# radfet_supply.net
KiCad netlist of a schematic drawn in Altium Designer
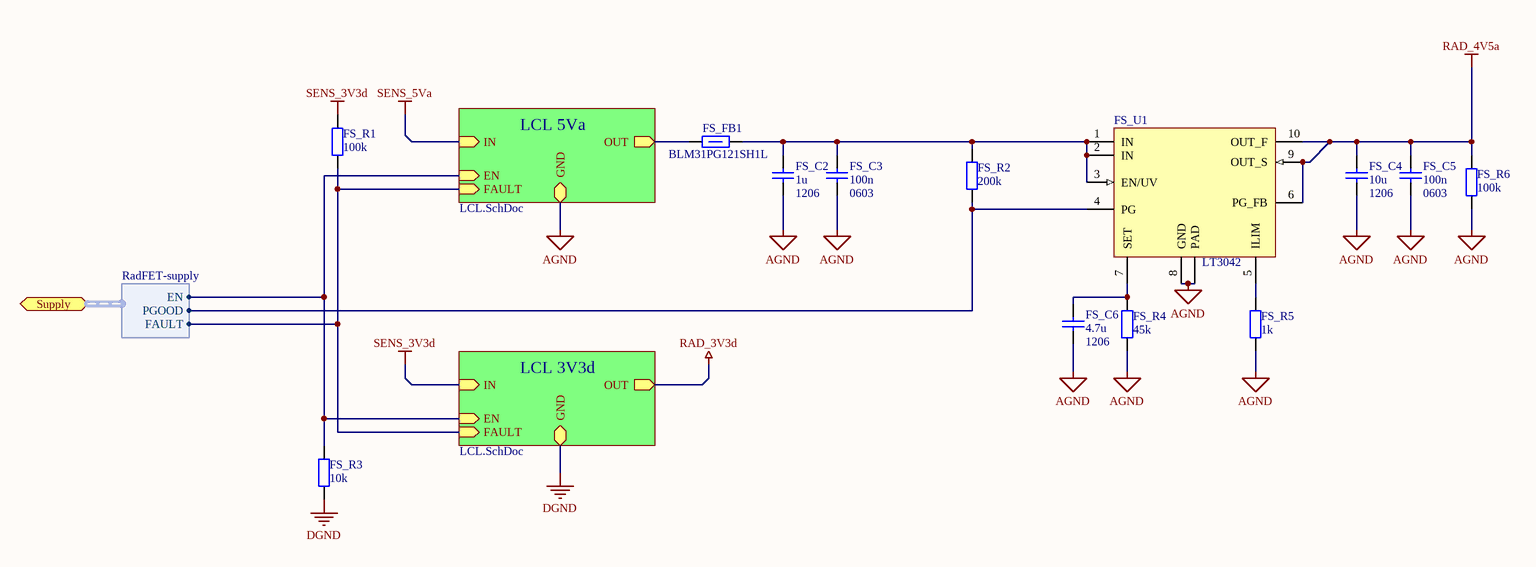
[diagram p0: radfet_supply.SchDoc]

(export (version "E")
  (design (tool "Eeschema 10.0.6"))
  (components
    (comp (ref "FS_C2")
      (value "1u")
      (footprint "SMD_Capacitor_1206")
      (description "Cap")
      (fields (field (name "PACKAGE") "1206"))
      (libsource (lib "capacitors") (part "Cap"))
    )
    (comp (ref "FS_C3")
      (value "100n")
      (footprint "SMD_Capacitor_0603")
      (description "Cap")
      (fields (field (name "PACKAGE") "0603"))
      (libsource (lib "capacitors") (part "Cap"))
    )
    (comp (ref "FS_C4")
      (value "10u")
      (footprint "SMD_Capacitor_1206")
      (description "Cap")
      (fields (field (name "PACKAGE") "1206"))
      (libsource (lib "capacitors") (part "Cap"))
    )
    (comp (ref "FS_C5")
      (value "100n")
      (footprint "SMD_Capacitor_0603")
      (description "Cap")
      (fields (field (name "PACKAGE") "0603"))
      (libsource (lib "capacitors") (part "Cap"))
    )
    (comp (ref "FS_C6")
      (value "4.7u")
      (footprint "SMD_Capacitor_1206")
      (description "Cap")
      (fields (field (name "PACKAGE") "1206"))
      (libsource (lib "capacitors") (part "Cap"))
    )
    (comp (ref "FS_FB1")
      (value "120R/100MHz")
      (footprint "SMD_FerriteBead_1206")
      (description "Ferrite bead, 1206, 0.02HM, 3.5A.")
      (fields (field (name "MANUFACTURER") "Murata") (field (name "MANUFACTURERPARTNUMBER") "BLM31PG121SH1L"))
      (libsource (lib "inductors") (part "BLM31PG121SH1L"))
    )
    (comp (ref "FS_R1")
      (value "100k")
      (footprint "SMD_Resistor_0603")
      (libsource (lib "resistors") (part "Res"))
    )
    (comp (ref "FS_R2") (value "200k") (footprint "SMD_Resistor_0603") (libsource (lib "") (part "Res_1")))
    (comp (ref "FS_R3")
      (value "10k")
      (footprint "SMD_Resistor_0603")
      (libsource (lib "resistors") (part "Res"))
    )
    (comp (ref "FS_R4")
      (value "45k")
      (footprint "SMD_Resistor_0603")
      (libsource (lib "resistors") (part "Res"))
    )
    (comp (ref "FS_R5")
      (value "1k")
      (footprint "SMD_Resistor_0603")
      (libsource (lib "resistors") (part "Res"))
    )
    (comp (ref "FS_R6")
      (value "100k")
      (footprint "SMD_Resistor_0603")
      (libsource (lib "resistors") (part "Res"))
    )
    (comp (ref "FS_U1")
      (value "LT3042")
      (footprint "MSOP-10-M-thermal-pad")
      (description "20V, 200mA, Ultralow Noise, Ultrahigh PSRR RF Linear Regulator")
      (libsource (lib "microcircuits") (part "LT3042"))
    )
  )
  (nets
    (net (code "2") (name "/EN") (class "Default")
      (node (ref "FS_R3") (pin "2") (pinfunction "2_2") (pintype "passive"))
    )
    (net (code "3") (name "/FAULT") (class "Default")
      (node (ref "FS_R1") (pin "1") (pinfunction "1_1") (pintype "passive"))
    )
    (net (code "4") (name "/OUT") (class "Default")
      (node (ref "FS_FB1") (pin "2") (pinfunction "2_2") (pintype "passive"))
    )
    (net (code "6") (name "AGND") (class "Default")
      (node (ref "FS_C2") (pin "2") (pinfunction "2_2") (pintype "passive"))
      (node (ref "FS_C3") (pin "2") (pinfunction "2_2") (pintype "passive"))
      (node (ref "FS_C4") (pin "2") (pinfunction "2_2") (pintype "passive"))
      (node (ref "FS_C5") (pin "2") (pinfunction "2_2") (pintype "passive"))
      (node (ref "FS_C6") (pin "2") (pinfunction "2_2") (pintype "passive"))
      (node (ref "FS_R4") (pin "1") (pinfunction "1_1") (pintype "passive"))
      (node (ref "FS_R5") (pin "1") (pinfunction "1_1") (pintype "passive"))
      (node (ref "FS_R6") (pin "1") (pinfunction "1_1") (pintype "passive"))
      (node (ref "FS_U1") (pin "11") (pinfunction "PAD_11") (pintype "power_in"))
      (node (ref "FS_U1") (pin "8") (pinfunction "GND_8") (pintype "power_in"))
    )
    (net (code "7") (name "DGND") (class "Default")
      (node (ref "FS_R3") (pin "1") (pinfunction "1_1") (pintype "passive"))
    )
    (net (code "8") (name "Net-(FS_U1-EN{slash}UV)") (class "Default")
      (node (ref "FS_C2") (pin "1") (pinfunction "1_1") (pintype "passive"))
      (node (ref "FS_C3") (pin "1") (pinfunction "1_1") (pintype "passive"))
      (node (ref "FS_FB1") (pin "1") (pinfunction "1_1") (pintype "passive"))
      (node (ref "FS_R2") (pin "1") (pinfunction "1_1") (pintype "passive"))
      (node (ref "FS_U1") (pin "1") (pinfunction "IN_1") (pintype "power_in"))
      (node (ref "FS_U1") (pin "2") (pinfunction "IN_2") (pintype "power_in"))
      (node (ref "FS_U1") (pin "3") (pinfunction "EN/UV_3") (pintype "input"))
    )
    (net (code "9") (name "Net-(FS_U1-ILIM)") (class "Default")
      (node (ref "FS_R5") (pin "2") (pinfunction "2_2") (pintype "passive"))
      (node (ref "FS_U1") (pin "5") (pinfunction "ILIM_5") (pintype "passive"))
    )
    (net (code "10") (name "Net-(FS_U1-PG)") (class "Default")
      (node (ref "FS_R2") (pin "2") (pinfunction "2_2") (pintype "passive"))
      (node (ref "FS_U1") (pin "4") (pinfunction "PG_4") (pintype "power_in"))
    )
    (net (code "11") (name "Net-(FS_U1-SET)") (class "Default")
      (node (ref "FS_C6") (pin "1") (pinfunction "1_1") (pintype "passive"))
      (node (ref "FS_R4") (pin "2") (pinfunction "2_2") (pintype "passive"))
      (node (ref "FS_U1") (pin "7") (pinfunction "SET_7") (pintype "passive"))
    )
    (net (code "13") (name "RAD_4V5a") (class "Default")
      (node (ref "FS_C4") (pin "1") (pinfunction "1_1") (pintype "passive"))
      (node (ref "FS_C5") (pin "1") (pinfunction "1_1") (pintype "passive"))
      (node (ref "FS_R6") (pin "2") (pinfunction "2_2") (pintype "passive"))
      (node (ref "FS_U1") (pin "10") (pinfunction "OUT_F_10") (pintype "power_in"))
      (node (ref "FS_U1") (pin "6") (pinfunction "PG_FB_6") (pintype "passive"))
      (node (ref "FS_U1") (pin "9") (pinfunction "OUT_S_9") (pintype "input"))
    )
    (net (code "14") (name "SENS_3V3d") (class "Default")
      (node (ref "FS_R1") (pin "2") (pinfunction "2_2") (pintype "passive"))
    )
  )
)
